# FOC_Drive.net
KiCad netlist of a schematic drawn in Altium Designer
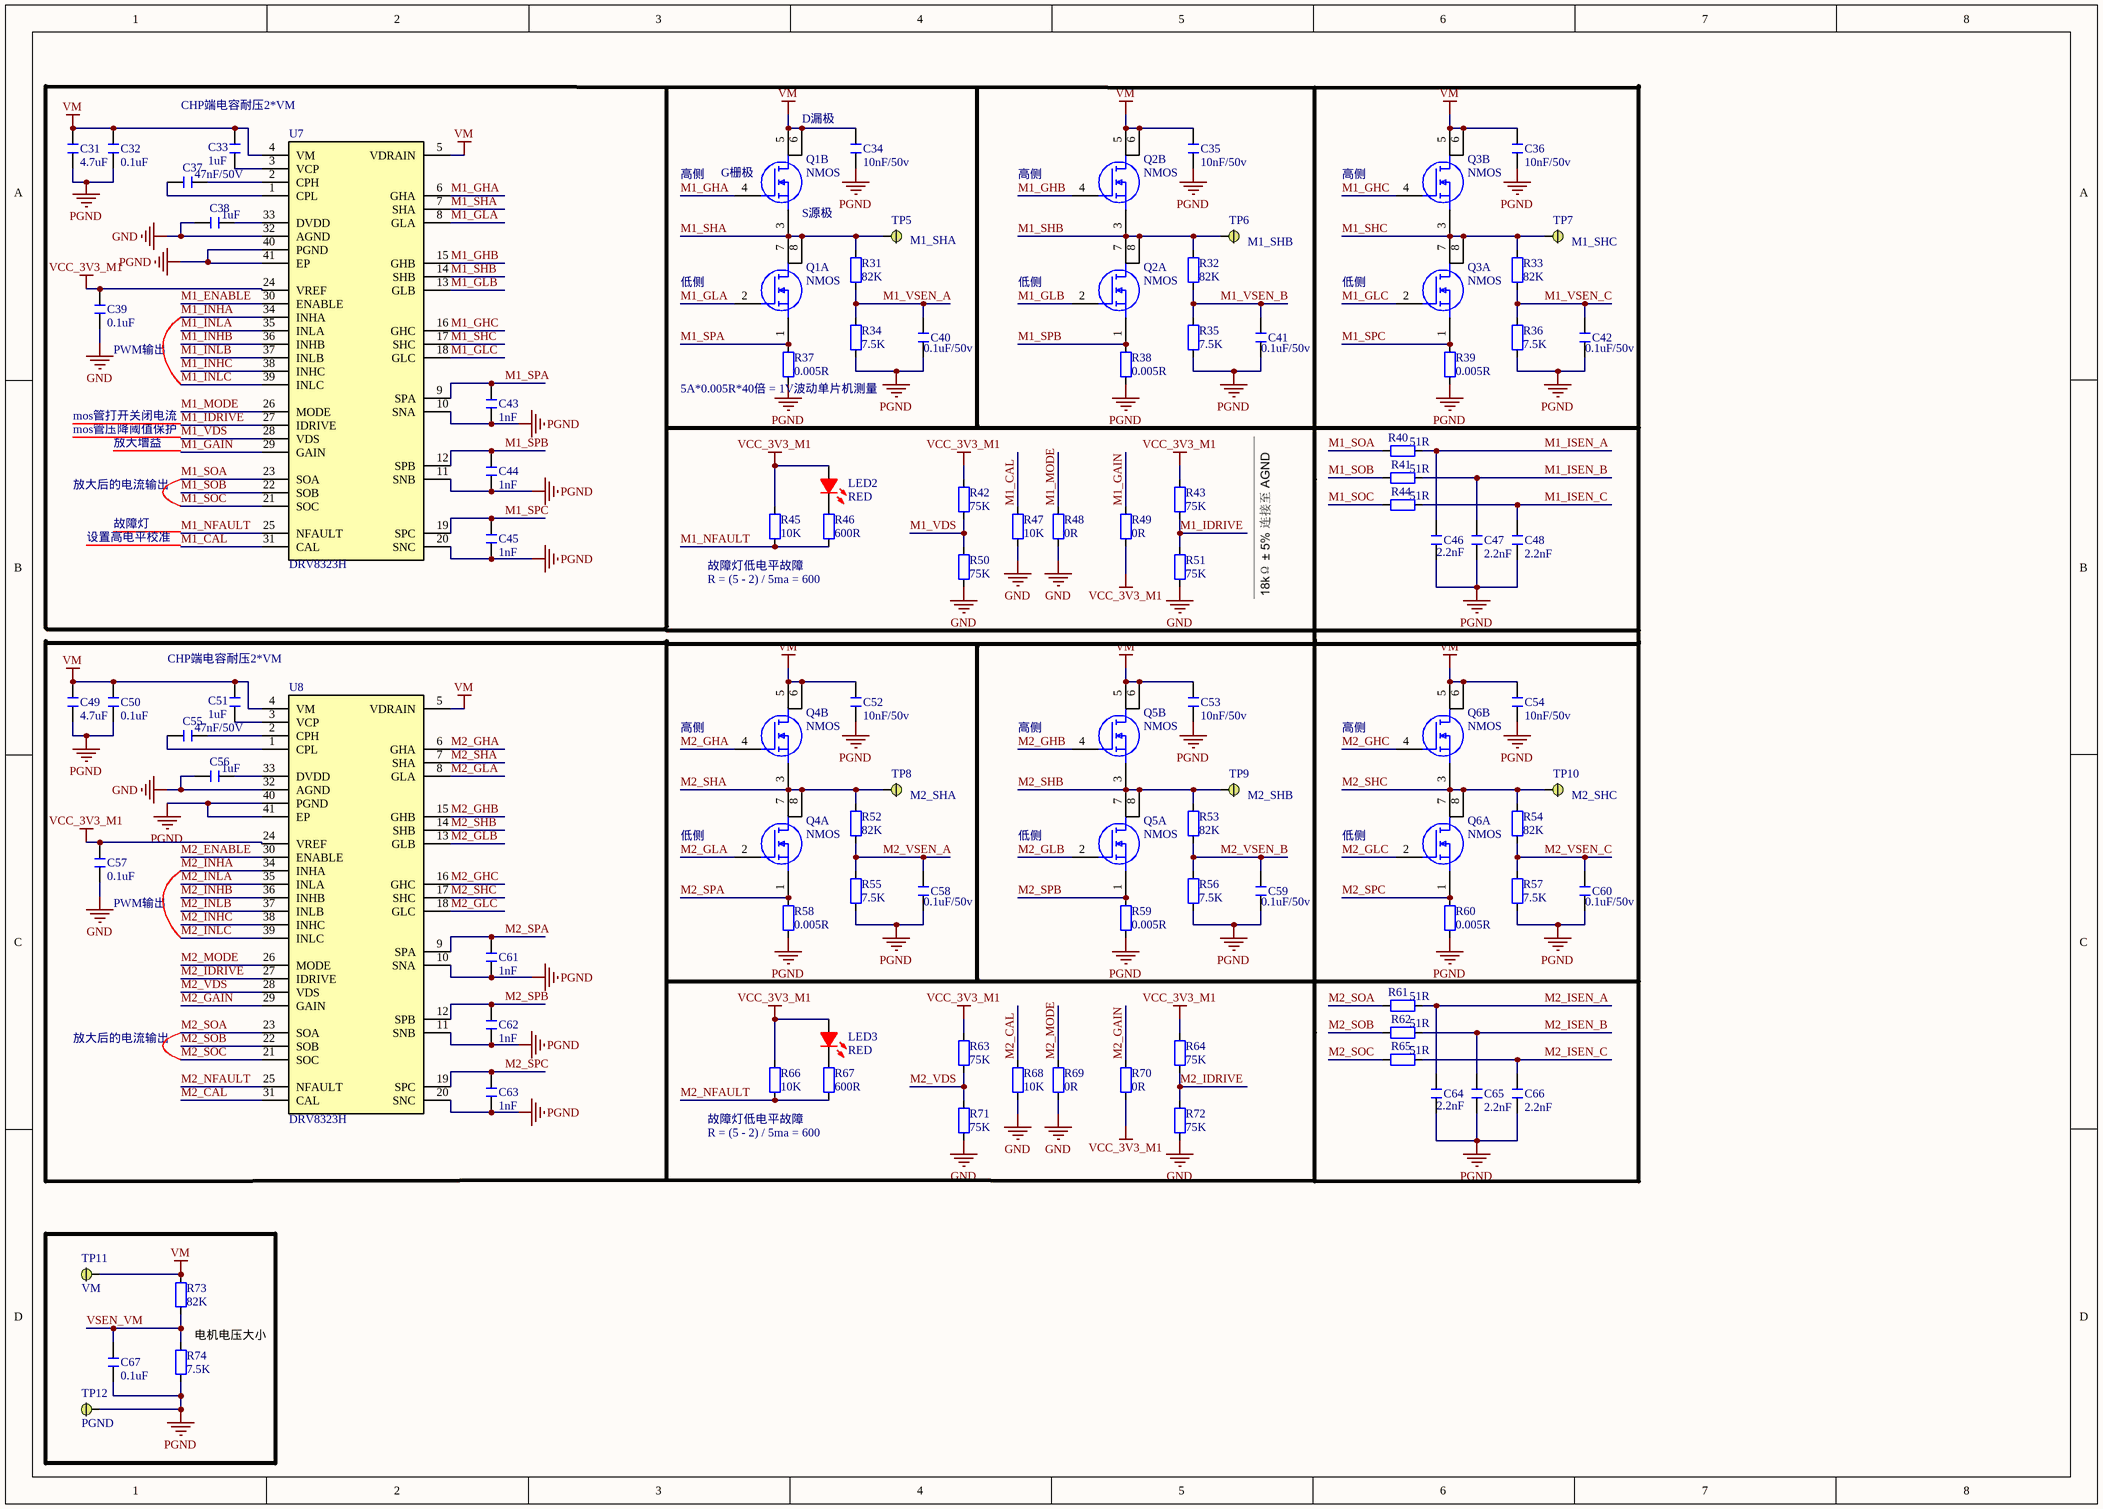
[diagram p0: FOC_Drive.SchDoc]

(export (version "E")
  (design (tool "Eeschema 10.0.6"))
  (components
    (comp (ref "C31")
      (value "4.7uF")
      (footprint "C 0603_L")
      (description "贴片电容")
      (libsource (lib "0.1 电阻_电容_电感") (part "C"))
    )
    (comp (ref "C32")
      (value "0.1uF")
      (footprint "C 0603_L")
      (description "贴片电容")
      (libsource (lib "0.1 电阻_电容_电感") (part "C"))
    )
    (comp (ref "C33")
      (value "1uF")
      (footprint "C 0603_L")
      (description "贴片电容")
      (libsource (lib "0.1 电阻_电容_电感") (part "C"))
    )
    (comp (ref "C34")
      (value "10nF/50v")
      (footprint "C 0603_L")
      (description "贴片电容")
      (libsource (lib "0.1 电阻_电容_电感") (part "C"))
    )
    (comp (ref "C35")
      (value "10nF/50v")
      (footprint "C 0603_L")
      (description "贴片电容")
      (libsource (lib "0.1 电阻_电容_电感") (part "C"))
    )
    (comp (ref "C36")
      (value "10nF/50v")
      (footprint "C 0603_L")
      (description "贴片电容")
      (libsource (lib "0.1 电阻_电容_电感") (part "C"))
    )
    (comp (ref "C37")
      (value "47nF/50V")
      (footprint "C 0603_L")
      (description "贴片电容")
      (libsource (lib "0.1 电阻_电容_电感") (part "C"))
    )
    (comp (ref "C38")
      (value "1uF")
      (footprint "C 0603_L")
      (description "贴片电容")
      (libsource (lib "0.1 电阻_电容_电感") (part "C"))
    )
    (comp (ref "C39")
      (value "0.1uF")
      (footprint "C 0603_L")
      (description "贴片电容")
      (libsource (lib "0.1 电阻_电容_电感") (part "C"))
    )
    (comp (ref "C40")
      (value "0.1uF/50v")
      (footprint "C 0603_L")
      (description "贴片电容")
      (libsource (lib "0.1 电阻_电容_电感") (part "C"))
    )
    (comp (ref "C41")
      (value "0.1uF/50v")
      (footprint "C 0603_L")
      (description "贴片电容")
      (libsource (lib "0.1 电阻_电容_电感") (part "C"))
    )
    (comp (ref "C42")
      (value "0.1uF/50v")
      (footprint "C 0603_L")
      (description "贴片电容")
      (libsource (lib "0.1 电阻_电容_电感") (part "C"))
    )
    (comp (ref "C43")
      (value "1nF")
      (footprint "C 0603_L")
      (description "贴片电容")
      (libsource (lib "0.1 电阻_电容_电感") (part "C"))
    )
    (comp (ref "C44")
      (value "1nF")
      (footprint "C 0603_L")
      (description "贴片电容")
      (libsource (lib "0.1 电阻_电容_电感") (part "C"))
    )
    (comp (ref "C45")
      (value "1nF")
      (footprint "C 0603_L")
      (description "贴片电容")
      (libsource (lib "0.1 电阻_电容_电感") (part "C"))
    )
    (comp (ref "C46")
      (value "2.2nF")
      (footprint "C 0603_L")
      (description "贴片电容")
      (libsource (lib "0.1 电阻_电容_电感") (part "C"))
    )
    (comp (ref "C47")
      (value "2.2nF")
      (footprint "C 0603_L")
      (description "贴片电容")
      (libsource (lib "0.1 电阻_电容_电感") (part "C"))
    )
    (comp (ref "C48")
      (value "2.2nF")
      (footprint "C 0603_L")
      (description "贴片电容")
      (libsource (lib "0.1 电阻_电容_电感") (part "C"))
    )
    (comp (ref "C49")
      (value "4.7uF")
      (footprint "C 0603_L")
      (description "贴片电容")
      (libsource (lib "0.1 电阻_电容_电感") (part "C"))
    )
    (comp (ref "C50")
      (value "0.1uF")
      (footprint "C 0603_L")
      (description "贴片电容")
      (libsource (lib "0.1 电阻_电容_电感") (part "C"))
    )
    (comp (ref "C51")
      (value "1uF")
      (footprint "C 0603_L")
      (description "贴片电容")
      (libsource (lib "0.1 电阻_电容_电感") (part "C"))
    )
    (comp (ref "C52")
      (value "10nF/50v")
      (footprint "C 0603_L")
      (description "贴片电容")
      (libsource (lib "0.1 电阻_电容_电感") (part "C"))
    )
    (comp (ref "C53")
      (value "10nF/50v")
      (footprint "C 0603_L")
      (description "贴片电容")
      (libsource (lib "0.1 电阻_电容_电感") (part "C"))
    )
    (comp (ref "C54")
      (value "10nF/50v")
      (footprint "C 0603_L")
      (description "贴片电容")
      (libsource (lib "0.1 电阻_电容_电感") (part "C"))
    )
    (comp (ref "C55")
      (value "47nF/50V")
      (footprint "C 0603_L")
      (description "贴片电容")
      (libsource (lib "0.1 电阻_电容_电感") (part "C"))
    )
    (comp (ref "C56")
      (value "1uF")
      (footprint "C 0603_L")
      (description "贴片电容")
      (libsource (lib "0.1 电阻_电容_电感") (part "C"))
    )
    (comp (ref "C57")
      (value "0.1uF")
      (footprint "C 0603_L")
      (description "贴片电容")
      (libsource (lib "0.1 电阻_电容_电感") (part "C"))
    )
    (comp (ref "C58")
      (value "0.1uF/50v")
      (footprint "C 0603_L")
      (description "贴片电容")
      (libsource (lib "0.1 电阻_电容_电感") (part "C"))
    )
    (comp (ref "C59")
      (value "0.1uF/50v")
      (footprint "C 0603_L")
      (description "贴片电容")
      (libsource (lib "0.1 电阻_电容_电感") (part "C"))
    )
    (comp (ref "C60")
      (value "0.1uF/50v")
      (footprint "C 0603_L")
      (description "贴片电容")
      (libsource (lib "0.1 电阻_电容_电感") (part "C"))
    )
    (comp (ref "C61")
      (value "1nF")
      (footprint "C 0603_L")
      (description "贴片电容")
      (libsource (lib "0.1 电阻_电容_电感") (part "C"))
    )
    (comp (ref "C62")
      (value "1nF")
      (footprint "C 0603_L")
      (description "贴片电容")
      (libsource (lib "0.1 电阻_电容_电感") (part "C"))
    )
    (comp (ref "C63")
      (value "1nF")
      (footprint "C 0603_L")
      (description "贴片电容")
      (libsource (lib "0.1 电阻_电容_电感") (part "C"))
    )
    (comp (ref "C64")
      (value "2.2nF")
      (footprint "C 0603_L")
      (description "贴片电容")
      (libsource (lib "0.1 电阻_电容_电感") (part "C"))
    )
    (comp (ref "C65")
      (value "2.2nF")
      (footprint "C 0603_L")
      (description "贴片电容")
      (libsource (lib "0.1 电阻_电容_电感") (part "C"))
    )
    (comp (ref "C66")
      (value "2.2nF")
      (footprint "C 0603_L")
      (description "贴片电容")
      (libsource (lib "0.1 电阻_电容_电感") (part "C"))
    )
    (comp (ref "C67")
      (value "0.1uF")
      (footprint "C 0603_L")
      (description "贴片电容")
      (libsource (lib "0.1 电阻_电容_电感") (part "C"))
    )
    (comp (ref "LED2")
      (value "RED")
      (footprint "LED_0603R")
      (description "贴片LED 0603 红色")
      (libsource (lib "0.6 发光二极管") (part "LED_R"))
    )
    (comp (ref "LED3")
      (value "RED")
      (footprint "LED_0603R")
      (description "贴片LED 0603 红色")
      (libsource (lib "0.6 发光二极管") (part "LED_R"))
    )
    (comp (ref "Q1")
      (value "NMOS")
      (footprint "DFN-8_L5.8-W4.9-P1.27-LS6.0-BL")
      (description "NMOS，100V，35A，2 channel")
      (libsource (lib "0.4 场效应管") (part "NCEP01ND35AG"))
    )
    (comp (ref "Q2")
      (value "NMOS")
      (footprint "DFN-8_L5.8-W4.9-P1.27-LS6.0-BL")
      (description "NMOS，100V，35A，2 channel")
      (libsource (lib "0.4 场效应管") (part "NCEP01ND35AG"))
    )
    (comp (ref "Q3")
      (value "NMOS")
      (footprint "DFN-8_L5.8-W4.9-P1.27-LS6.0-BL")
      (description "NMOS，100V，35A，2 channel")
      (libsource (lib "0.4 场效应管") (part "NCEP01ND35AG"))
    )
    (comp (ref "Q4")
      (value "NMOS")
      (footprint "DFN-8_L5.8-W4.9-P1.27-LS6.0-BL")
      (description "NMOS，100V，35A，2 channel")
      (libsource (lib "0.4 场效应管") (part "NCEP01ND35AG"))
    )
    (comp (ref "Q5")
      (value "NMOS")
      (footprint "DFN-8_L5.8-W4.9-P1.27-LS6.0-BL")
      (description "NMOS，100V，35A，2 channel")
      (libsource (lib "0.4 场效应管") (part "NCEP01ND35AG"))
    )
    (comp (ref "Q6")
      (value "NMOS")
      (footprint "DFN-8_L5.8-W4.9-P1.27-LS6.0-BL")
      (description "NMOS，100V，35A，2 channel")
      (libsource (lib "0.4 场效应管") (part "NCEP01ND35AG"))
    )
    (comp (ref "R31")
      (value "82K")
      (footprint "R 0603_L")
      (description "贴片电阻")
      (libsource (lib "0.1 电阻_电容_电感") (part "R"))
    )
    (comp (ref "R32")
      (value "82K")
      (footprint "R 0603_L")
      (description "贴片电阻")
      (libsource (lib "0.1 电阻_电容_电感") (part "R"))
    )
    (comp (ref "R33")
      (value "82K")
      (footprint "R 0603_L")
      (description "贴片电阻")
      (libsource (lib "0.1 电阻_电容_电感") (part "R"))
    )
    (comp (ref "R34")
      (value "7.5K")
      (footprint "R 0603_L")
      (description "贴片电阻")
      (libsource (lib "0.1 电阻_电容_电感") (part "R"))
    )
    (comp (ref "R35")
      (value "7.5K")
      (footprint "R 0603_L")
      (description "贴片电阻")
      (libsource (lib "0.1 电阻_电容_电感") (part "R"))
    )
    (comp (ref "R36")
      (value "7.5K")
      (footprint "R 0603_L")
      (description "贴片电阻")
      (libsource (lib "0.1 电阻_电容_电感") (part "R"))
    )
    (comp (ref "R37")
      (value "0.005R")
      (footprint "R 2512_L")
      (description "贴片电阻")
      (libsource (lib "0.1 电阻_电容_电感") (part "R"))
    )
    (comp (ref "R38")
      (value "0.005R")
      (footprint "R 2512_L")
      (description "贴片电阻")
      (libsource (lib "0.1 电阻_电容_电感") (part "R"))
    )
    (comp (ref "R39")
      (value "0.005R")
      (footprint "R 2512_L")
      (description "贴片电阻")
      (libsource (lib "0.1 电阻_电容_电感") (part "R"))
    )
    (comp (ref "R40")
      (value "51R")
      (footprint "R 0603_L")
      (description "贴片电阻")
      (libsource (lib "") (part "R_2"))
    )
    (comp (ref "R41")
      (value "51R")
      (footprint "R 0603_L")
      (description "贴片电阻")
      (libsource (lib "") (part "R_2"))
    )
    (comp (ref "R42")
      (value "75K")
      (footprint "R 0603_L")
      (description "贴片电阻")
      (libsource (lib "") (part "R_1"))
    )
    (comp (ref "R43")
      (value "75K")
      (footprint "R 0603_L")
      (description "贴片电阻")
      (libsource (lib "") (part "R_1"))
    )
    (comp (ref "R44")
      (value "51R")
      (footprint "R 0603_L")
      (description "贴片电阻")
      (libsource (lib "") (part "R_2"))
    )
    (comp (ref "R45")
      (value "10K")
      (footprint "R 0603_L")
      (description "贴片电阻")
      (libsource (lib "") (part "R_1"))
    )
    (comp (ref "R46")
      (value "600R")
      (footprint "R 0603_L")
      (description "贴片电阻")
      (libsource (lib "") (part "R_1"))
    )
    (comp (ref "R47")
      (value "10K")
      (footprint "R 0603_L")
      (description "贴片电阻")
      (libsource (lib "") (part "R_1"))
    )
    (comp (ref "R48")
      (value "0R")
      (footprint "R 0603_L")
      (description "贴片电阻")
      (libsource (lib "0.1 电阻_电容_电感") (part "R"))
    )
    (comp (ref "R49")
      (value "0R")
      (footprint "R 0603_L")
      (description "贴片电阻")
      (libsource (lib "0.1 电阻_电容_电感") (part "R"))
    )
    (comp (ref "R50")
      (value "75K")
      (footprint "R 0603_L")
      (description "贴片电阻")
      (libsource (lib "") (part "R_1"))
    )
    (comp (ref "R51")
      (value "75K")
      (footprint "R 0603_L")
      (description "贴片电阻")
      (libsource (lib "") (part "R_1"))
    )
    (comp (ref "R52")
      (value "82K")
      (footprint "R 0603_L")
      (description "贴片电阻")
      (libsource (lib "0.1 电阻_电容_电感") (part "R"))
    )
    (comp (ref "R53")
      (value "82K")
      (footprint "R 0603_L")
      (description "贴片电阻")
      (libsource (lib "0.1 电阻_电容_电感") (part "R"))
    )
    (comp (ref "R54")
      (value "82K")
      (footprint "R 0603_L")
      (description "贴片电阻")
      (libsource (lib "0.1 电阻_电容_电感") (part "R"))
    )
    (comp (ref "R55")
      (value "7.5K")
      (footprint "R 0603_L")
      (description "贴片电阻")
      (libsource (lib "0.1 电阻_电容_电感") (part "R"))
    )
    (comp (ref "R56")
      (value "7.5K")
      (footprint "R 0603_L")
      (description "贴片电阻")
      (libsource (lib "0.1 电阻_电容_电感") (part "R"))
    )
    (comp (ref "R57")
      (value "7.5K")
      (footprint "R 0603_L")
      (description "贴片电阻")
      (libsource (lib "0.1 电阻_电容_电感") (part "R"))
    )
    (comp (ref "R58")
      (value "0.005R")
      (footprint "R 2512_L")
      (description "贴片电阻")
      (libsource (lib "0.1 电阻_电容_电感") (part "R"))
    )
    (comp (ref "R59")
      (value "0.005R")
      (footprint "R 2512_L")
      (description "贴片电阻")
      (libsource (lib "0.1 电阻_电容_电感") (part "R"))
    )
    (comp (ref "R60")
      (value "0.005R")
      (footprint "R 2512_L")
      (description "贴片电阻")
      (libsource (lib "0.1 电阻_电容_电感") (part "R"))
    )
    (comp (ref "R61")
      (value "51R")
      (footprint "R 0603_L")
      (description "贴片电阻")
      (libsource (lib "") (part "R_2"))
    )
    (comp (ref "R62")
      (value "51R")
      (footprint "R 0603_L")
      (description "贴片电阻")
      (libsource (lib "") (part "R_2"))
    )
    (comp (ref "R63")
      (value "75K")
      (footprint "R 0603_L")
      (description "贴片电阻")
      (libsource (lib "") (part "R_1"))
    )
    (comp (ref "R64")
      (value "75K")
      (footprint "R 0603_L")
      (description "贴片电阻")
      (libsource (lib "") (part "R_1"))
    )
    (comp (ref "R65")
      (value "51R")
      (footprint "R 0603_L")
      (description "贴片电阻")
      (libsource (lib "") (part "R_2"))
    )
    (comp (ref "R66")
      (value "10K")
      (footprint "R 0603_L")
      (description "贴片电阻")
      (libsource (lib "") (part "R_1"))
    )
    (comp (ref "R67")
      (value "600R")
      (footprint "R 0603_L")
      (description "贴片电阻")
      (libsource (lib "") (part "R_1"))
    )
    (comp (ref "R68")
      (value "10K")
      (footprint "R 0603_L")
      (description "贴片电阻")
      (libsource (lib "") (part "R_1"))
    )
    (comp (ref "R69")
      (value "0R")
      (footprint "R 0603_L")
      (description "贴片电阻")
      (libsource (lib "0.1 电阻_电容_电感") (part "R"))
    )
    (comp (ref "R70")
      (value "0R")
      (footprint "R 0603_L")
      (description "贴片电阻")
      (libsource (lib "0.1 电阻_电容_电感") (part "R"))
    )
    (comp (ref "R71")
      (value "75K")
      (footprint "R 0603_L")
      (description "贴片电阻")
      (libsource (lib "") (part "R_1"))
    )
    (comp (ref "R72")
      (value "75K")
      (footprint "R 0603_L")
      (description "贴片电阻")
      (libsource (lib "") (part "R_1"))
    )
    (comp (ref "R73")
      (value "82K")
      (footprint "R 0603_L")
      (description "贴片电阻")
      (libsource (lib "") (part "R_1"))
    )
    (comp (ref "R74")
      (value "7.5K")
      (footprint "R 0603_L")
      (description "贴片电阻")
      (libsource (lib "") (part "R_1"))
    )
    (comp (ref "TP5") (value "M1_SHA") (footprint "TP_RECT_2x2") (libsource (lib "0.5 测试点-焊盘") (part "TP")))
    (comp (ref "TP6") (value "M1_SHB") (footprint "TP_RECT_2x2") (libsource (lib "0.5 测试点-焊盘") (part "TP")))
    (comp (ref "TP7") (value "M1_SHC") (footprint "TP_RECT_2x2") (libsource (lib "0.5 测试点-焊盘") (part "TP")))
    (comp (ref "TP8") (value "M2_SHA") (footprint "TP_RECT_2x2") (libsource (lib "0.5 测试点-焊盘") (part "TP")))
    (comp (ref "TP9") (value "M2_SHB") (footprint "TP_RECT_2x2") (libsource (lib "0.5 测试点-焊盘") (part "TP")))
    (comp (ref "TP10") (value "M2_SHC") (footprint "TP_RECT_2x2") (libsource (lib "0.5 测试点-焊盘") (part "TP")))
    (comp (ref "TP11") (value "VM") (footprint "TP_RECT_2x2") (libsource (lib "0.5 测试点-焊盘") (part "TP")))
    (comp (ref "TP12") (value "PGND") (footprint "TP_RECT_2x2") (libsource (lib "0.5 测试点-焊盘") (part "TP")))
    (comp (ref "U7")
      (value "DRV8323H")
      (footprint "QFN50P600X600X80-41N-D")
      (description "三相智能栅极驱动器")
      (fields (field (name "MANUFACTURER_PART_NUMBER") "DRV8323"))
      (libsource (lib "0.4 场效应管") (part "DRV8323H"))
    )
    (comp (ref "U8")
      (value "DRV8323H")
      (footprint "QFN50P600X600X80-41N-D")
      (description "三相智能栅极驱动器")
      (fields (field (name "MANUFACTURER_PART_NUMBER") "DRV8323"))
      (libsource (lib "0.4 场效应管") (part "DRV8323H"))
    )
  )
  (nets
    (net (code "1") (name "/M1_CAL") (class "Default")
      (node (ref "R47") (pin "1") (pinfunction "1_1") (pintype "passive"))
      (node (ref "U7") (pin "31") (pinfunction "CAL_31") (pintype "passive"))
    )
    (net (code "2") (name "/M1_ENABLE") (class "Default")
      (node (ref "U7") (pin "30") (pinfunction "ENABLE_30") (pintype "passive"))
    )
    (net (code "3") (name "/M1_GAIN") (class "Default")
      (node (ref "R49") (pin "2") (pinfunction "2_2") (pintype "passive"))
      (node (ref "U7") (pin "29") (pinfunction "GAIN_29") (pintype "passive"))
    )
    (net (code "4") (name "/M1_GHA") (class "Default")
      (node (ref "Q1") (pin "4") (pinfunction "G2_4") (pintype "passive"))
      (node (ref "U7") (pin "6") (pinfunction "GHA_6") (pintype "passive"))
    )
    (net (code "5") (name "/M1_GHB") (class "Default")
      (node (ref "Q2") (pin "4") (pinfunction "G2_4") (pintype "passive"))
      (node (ref "U7") (pin "15") (pinfunction "GHB_15") (pintype "passive"))
    )
    (net (code "6") (name "/M1_GHC") (class "Default")
      (node (ref "Q3") (pin "4") (pinfunction "G2_4") (pintype "passive"))
      (node (ref "U7") (pin "16") (pinfunction "GHC_16") (pintype "passive"))
    )
    (net (code "7") (name "/M1_GLA") (class "Default")
      (node (ref "Q1") (pin "2") (pinfunction "G1_2") (pintype "passive"))
      (node (ref "U7") (pin "8") (pinfunction "GLA_8") (pintype "passive"))
    )
    (net (code "8") (name "/M1_GLB") (class "Default")
      (node (ref "Q2") (pin "2") (pinfunction "G1_2") (pintype "passive"))
      (node (ref "U7") (pin "13") (pinfunction "GLB_13") (pintype "passive"))
    )
    (net (code "9") (name "/M1_GLC") (class "Default")
      (node (ref "Q3") (pin "2") (pinfunction "G1_2") (pintype "passive"))
      (node (ref "U7") (pin "18") (pinfunction "GLC_18") (pintype "passive"))
    )
    (net (code "10") (name "/M1_IDRIVE") (class "Default")
      (node (ref "R43") (pin "2") (pinfunction "2_2") (pintype "passive"))
      (node (ref "R51") (pin "1") (pinfunction "1_1") (pintype "passive"))
      (node (ref "U7") (pin "27") (pinfunction "IDRIVE_27") (pintype "passive"))
    )
    (net (code "11") (name "/M1_INHA") (class "Default")
      (node (ref "U7") (pin "34") (pinfunction "INHA_34") (pintype "passive"))
    )
    (net (code "12") (name "/M1_INHB") (class "Default")
      (node (ref "U7") (pin "36") (pinfunction "INHB_36") (pintype "passive"))
    )
    (net (code "13") (name "/M1_INHC") (class "Default")
      (node (ref "U7") (pin "38") (pinfunction "INHC_38") (pintype "passive"))
    )
    (net (code "14") (name "/M1_INLA") (class "Default")
      (node (ref "U7") (pin "35") (pinfunction "INLA_35") (pintype "passive"))
    )
    (net (code "15") (name "/M1_INLB") (class "Default")
      (node (ref "U7") (pin "37") (pinfunction "INLB_37") (pintype "passive"))
    )
    (net (code "16") (name "/M1_INLC") (class "Default")
      (node (ref "U7") (pin "39") (pinfunction "INLC_39") (pintype "passive"))
    )
    (net (code "17") (name "/M1_ISEN_A") (class "Default")
      (node (ref "C46") (pin "2") (pinfunction "2_2") (pintype "passive"))
      (node (ref "R40") (pin "1") (pinfunction "1_1") (pintype "passive"))
    )
    (net (code "18") (name "/M1_ISEN_B") (class "Default")
      (node (ref "C47") (pin "2") (pinfunction "2_2") (pintype "passive"))
      (node (ref "R41") (pin "1") (pinfunction "1_1") (pintype "passive"))
    )
    (net (code "19") (name "/M1_ISEN_C") (class "Default")
      (node (ref "C48") (pin "2") (pinfunction "2_2") (pintype "passive"))
      (node (ref "R44") (pin "1") (pinfunction "1_1") (pintype "passive"))
    )
    (net (code "20") (name "/M1_MODE") (class "Default")
      (node (ref "R48") (pin "2") (pinfunction "2_2") (pintype "passive"))
      (node (ref "U7") (pin "26") (pinfunction "MODE_26") (pintype "passive"))
    )
    (net (code "21") (name "/M1_NFAULT") (class "Default")
      (node (ref "R45") (pin "2") (pinfunction "2_2") (pintype "passive"))
      (node (ref "R46") (pin "2") (pinfunction "2_2") (pintype "passive"))
      (node (ref "U7") (pin "25") (pinfunction "NFAULT_25") (pintype "passive"))
    )
    (net (code "22") (name "/M1_SHA") (class "Default")
      (node (ref "Q1") (pin "3") (pinfunction "S2_3") (pintype "passive"))
      (node (ref "Q1") (pin "7") (pinfunction "D1_7") (pintype "passive"))
      (node (ref "Q1") (pin "8") (pinfunction "D1_8") (pintype "passive"))
      (node (ref "R31") (pin "2") (pinfunction "2_2") (pintype "passive"))
      (node (ref "TP5") (pin "1") (pintype "passive"))
      (node (ref "U7") (pin "7") (pinfunction "SHA_7") (pintype "passive"))
    )
    (net (code "23") (name "/M1_SHB") (class "Default")
      (node (ref "Q2") (pin "3") (pinfunction "S2_3") (pintype "passive"))
      (node (ref "Q2") (pin "7") (pinfunction "D1_7") (pintype "passive"))
      (node (ref "Q2") (pin "8") (pinfunction "D1_8") (pintype "passive"))
      (node (ref "R32") (pin "2") (pinfunction "2_2") (pintype "passive"))
      (node (ref "TP6") (pin "1") (pintype "passive"))
      (node (ref "U7") (pin "14") (pinfunction "SHB_14") (pintype "passive"))
    )
    (net (code "24") (name "/M1_SHC") (class "Default")
      (node (ref "Q3") (pin "3") (pinfunction "S2_3") (pintype "passive"))
      (node (ref "Q3") (pin "7") (pinfunction "D1_7") (pintype "passive"))
      (node (ref "Q3") (pin "8") (pinfunction "D1_8") (pintype "passive"))
      (node (ref "R33") (pin "2") (pinfunction "2_2") (pintype "passive"))
      (node (ref "TP7") (pin "1") (pintype "passive"))
      (node (ref "U7") (pin "17") (pinfunction "SHC_17") (pintype "passive"))
    )
    (net (code "25") (name "/M1_SOA") (class "Default")
      (node (ref "R40") (pin "2") (pinfunction "2_2") (pintype "passive"))
      (node (ref "U7") (pin "23") (pinfunction "SOA_23") (pintype "passive"))
    )
    (net (code "26") (name "/M1_SOB") (class "Default")
      (node (ref "R41") (pin "2") (pinfunction "2_2") (pintype "passive"))
      (node (ref "U7") (pin "22") (pinfunction "SOB_22") (pintype "passive"))
    )
    (net (code "27") (name "/M1_SOC") (class "Default")
      (node (ref "R44") (pin "2") (pinfunction "2_2") (pintype "passive"))
      (node (ref "U7") (pin "21") (pinfunction "SOC_21") (pintype "passive"))
    )
    (net (code "28") (name "/M1_SPA") (class "Default")
      (node (ref "C43") (pin "1") (pinfunction "1_1") (pintype "passive"))
      (node (ref "Q1") (pin "1") (pinfunction "S1_1") (pintype "passive"))
      (node (ref "R37") (pin "2") (pinfunction "2_2") (pintype "passive"))
      (node (ref "U7") (pin "9") (pinfunction "SPA_9") (pintype "passive"))
    )
    (net (code "29") (name "/M1_SPB") (class "Default")
      (node (ref "C44") (pin "1") (pinfunction "1_1") (pintype "passive"))
      (node (ref "Q2") (pin "1") (pinfunction "S1_1") (pintype "passive"))
      (node (ref "R38") (pin "2") (pinfunction "2_2") (pintype "passive"))
      (node (ref "U7") (pin "12") (pinfunction "SPB_12") (pintype "passive"))
    )
    (net (code "30") (name "/M1_SPC") (class "Default")
      (node (ref "C45") (pin "1") (pinfunction "1_1") (pintype "passive"))
      (node (ref "Q3") (pin "1") (pinfunction "S1_1") (pintype "passive"))
      (node (ref "R39") (pin "2") (pinfunction "2_2") (pintype "passive"))
      (node (ref "U7") (pin "19") (pinfunction "SPC_19") (pintype "passive"))
    )
    (net (code "31") (name "/M1_VDS") (class "Default")
      (node (ref "R42") (pin "2") (pinfunction "2_2") (pintype "passive"))
      (node (ref "R50") (pin "1") (pinfunction "1_1") (pintype "passive"))
      (node (ref "U7") (pin "28") (pinfunction "VDS_28") (pintype "passive"))
    )
    (net (code "32") (name "/M1_VSEN_A") (class "Default")
      (node (ref "C40") (pin "2") (pinfunction "2_2") (pintype "passive"))
      (node (ref "R31") (pin "1") (pinfunction "1_1") (pintype "passive"))
      (node (ref "R34") (pin "2") (pinfunction "2_2") (pintype "passive"))
    )
    (net (code "33") (name "/M1_VSEN_B") (class "Default")
      (node (ref "C41") (pin "2") (pinfunction "2_2") (pintype "passive"))
      (node (ref "R32") (pin "1") (pinfunction "1_1") (pintype "passive"))
      (node (ref "R35") (pin "2") (pinfunction "2_2") (pintype "passive"))
    )
    (net (code "34") (name "/M1_VSEN_C") (class "Default")
      (node (ref "C42") (pin "2") (pinfunction "2_2") (pintype "passive"))
      (node (ref "R33") (pin "1") (pinfunction "1_1") (pintype "passive"))
      (node (ref "R36") (pin "2") (pinfunction "2_2") (pintype "passive"))
    )
    (net (code "35") (name "/M2_CAL") (class "Default")
      (node (ref "R68") (pin "1") (pinfunction "1_1") (pintype "passive"))
      (node (ref "U8") (pin "31") (pinfunction "CAL_31") (pintype "passive"))
    )
    (net (code "36") (name "/M2_ENABLE") (class "Default")
      (node (ref "U8") (pin "30") (pinfunction "ENABLE_30") (pintype "passive"))
    )
    (net (code "37") (name "/M2_GAIN") (class "Default")
      (node (ref "R70") (pin "2") (pinfunction "2_2") (pintype "passive"))
      (node (ref "U8") (pin "29") (pinfunction "GAIN_29") (pintype "passive"))
    )
    (net (code "38") (name "/M2_GHA") (class "Default")
      (node (ref "Q4") (pin "4") (pinfunction "G2_4") (pintype "passive"))
      (node (ref "U8") (pin "6") (pinfunction "GHA_6") (pintype "passive"))
    )
    (net (code "39") (name "/M2_GHB") (class "Default")
      (node (ref "Q5") (pin "4") (pinfunction "G2_4") (pintype "passive"))
      (node (ref "U8") (pin "15") (pinfunction "GHB_15") (pintype "passive"))
    )
    (net (code "40") (name "/M2_GHC") (class "Default")
      (node (ref "Q6") (pin "4") (pinfunction "G2_4") (pintype "passive"))
      (node (ref "U8") (pin "16") (pinfunction "GHC_16") (pintype "passive"))
    )
    (net (code "41") (name "/M2_GLA") (class "Default")
      (node (ref "Q4") (pin "2") (pinfunction "G1_2") (pintype "passive"))
      (node (ref "U8") (pin "8") (pinfunction "GLA_8") (pintype "passive"))
    )
    (net (code "42") (name "/M2_GLB") (class "Default")
      (node (ref "Q5") (pin "2") (pinfunction "G1_2") (pintype "passive"))
      (node (ref "U8") (pin "13") (pinfunction "GLB_13") (pintype "passive"))
    )
    (net (code "43") (name "/M2_GLC") (class "Default")
      (node (ref "Q6") (pin "2") (pinfunction "G1_2") (pintype "passive"))
      (node (ref "U8") (pin "18") (pinfunction "GLC_18") (pintype "passive"))
    )
    (net (code "44") (name "/M2_IDRIVE") (class "Default")
      (node (ref "R64") (pin "2") (pinfunction "2_2") (pintype "passive"))
      (node (ref "R72") (pin "1") (pinfunction "1_1") (pintype "passive"))
      (node (ref "U8") (pin "27") (pinfunction "IDRIVE_27") (pintype "passive"))
    )
    (net (code "45") (name "/M2_INHA") (class "Default")
      (node (ref "U8") (pin "34") (pinfunction "INHA_34") (pintype "passive"))
    )
    (net (code "46") (name "/M2_INHB") (class "Default")
      (node (ref "U8") (pin "36") (pinfunction "INHB_36") (pintype "passive"))
    )
    (net (code "47") (name "/M2_INHC") (class "Default")
      (node (ref "U8") (pin "38") (pinfunction "INHC_38") (pintype "passive"))
    )
    (net (code "48") (name "/M2_INLA") (class "Default")
      (node (ref "U8") (pin "35") (pinfunction "INLA_35") (pintype "passive"))
    )
    (net (code "49") (name "/M2_INLB") (class "Default")
      (node (ref "U8") (pin "37") (pinfunction "INLB_37") (pintype "passive"))
    )
    (net (code "50") (name "/M2_INLC") (class "Default")
      (node (ref "U8") (pin "39") (pinfunction "INLC_39") (pintype "passive"))
    )
    (net (code "51") (name "/M2_ISEN_A") (class "Default")
      (node (ref "C64") (pin "2") (pinfunction "2_2") (pintype "passive"))
      (node (ref "R61") (pin "1") (pinfunction "1_1") (pintype "passive"))
    )
    (net (code "52") (name "/M2_ISEN_B") (class "Default")
      (node (ref "C65") (pin "2") (pinfunction "2_2") (pintype "passive"))
      (node (ref "R62") (pin "1") (pinfunction "1_1") (pintype "passive"))
    )
    (net (code "53") (name "/M2_ISEN_C") (class "Default")
      (node (ref "C66") (pin "2") (pinfunction "2_2") (pintype "passive"))
      (node (ref "R65") (pin "1") (pinfunction "1_1") (pintype "passive"))
    )
    (net (code "54") (name "/M2_MODE") (class "Default")
      (node (ref "R69") (pin "2") (pinfunction "2_2") (pintype "passive"))
      (node (ref "U8") (pin "26") (pinfunction "MODE_26") (pintype "passive"))
    )
    (net (code "55") (name "/M2_NFAULT") (class "Default")
      (node (ref "R66") (pin "2") (pinfunction "2_2") (pintype "passive"))
      (node (ref "R67") (pin "2") (pinfunction "2_2") (pintype "passive"))
      (node (ref "U8") (pin "25") (pinfunction "NFAULT_25") (pintype "passive"))
    )
    (net (code "56") (name "/M2_SHA") (class "Default")
      (node (ref "Q4") (pin "3") (pinfunction "S2_3") (pintype "passive"))
      (node (ref "Q4") (pin "7") (pinfunction "D1_7") (pintype "passive"))
      (node (ref "Q4") (pin "8") (pinfunction "D1_8") (pintype "passive"))
      (node (ref "R52") (pin "2") (pinfunction "2_2") (pintype "passive"))
      (node (ref "TP8") (pin "1") (pintype "passive"))
      (node (ref "U8") (pin "7") (pinfunction "SHA_7") (pintype "passive"))
    )
    (net (code "57") (name "/M2_SHB") (class "Default")
      (node (ref "Q5") (pin "3") (pinfunction "S2_3") (pintype "passive"))
      (node (ref "Q5") (pin "7") (pinfunction "D1_7") (pintype "passive"))
      (node (ref "Q5") (pin "8") (pinfunction "D1_8") (pintype "passive"))
      (node (ref "R53") (pin "2") (pinfunction "2_2") (pintype "passive"))
      (node (ref "TP9") (pin "1") (pintype "passive"))
      (node (ref "U8") (pin "14") (pinfunction "SHB_14") (pintype "passive"))
    )
    (net (code "58") (name "/M2_SHC") (class "Default")
      (node (ref "Q6") (pin "3") (pinfunction "S2_3") (pintype "passive"))
      (node (ref "Q6") (pin "7") (pinfunction "D1_7") (pintype "passive"))
      (node (ref "Q6") (pin "8") (pinfunction "D1_8") (pintype "passive"))
      (node (ref "R54") (pin "2") (pinfunction "2_2") (pintype "passive"))
      (node (ref "TP10") (pin "1") (pintype "passive"))
      (node (ref "U8") (pin "17") (pinfunction "SHC_17") (pintype "passive"))
    )
    (net (code "59") (name "/M2_SOA") (class "Default")
      (node (ref "R61") (pin "2") (pinfunction "2_2") (pintype "passive"))
      (node (ref "U8") (pin "23") (pinfunction "SOA_23") (pintype "passive"))
    )
    (net (code "60") (name "/M2_SOB") (class "Default")
      (node (ref "R62") (pin "2") (pinfunction "2_2") (pintype "passive"))
      (node (ref "U8") (pin "22") (pinfunction "SOB_22") (pintype "passive"))
    )
    (net (code "61") (name "/M2_SOC") (class "Default")
      (node (ref "R65") (pin "2") (pinfunction "2_2") (pintype "passive"))
      (node (ref "U8") (pin "21") (pinfunction "SOC_21") (pintype "passive"))
    )
    (net (code "62") (name "/M2_SPA") (class "Default")
      (node (ref "C61") (pin "1") (pinfunction "1_1") (pintype "passive"))
      (node (ref "Q4") (pin "1") (pinfunction "S1_1") (pintype "passive"))
      (node (ref "R58") (pin "2") (pinfunction "2_2") (pintype "passive"))
      (node (ref "U8") (pin "9") (pinfunction "SPA_9") (pintype "passive"))
    )
    (net (code "63") (name "/M2_SPB") (class "Default")
      (node (ref "C62") (pin "1") (pinfunction "1_1") (pintype "passive"))
      (node (ref "Q5") (pin "1") (pinfunction "S1_1") (pintype "passive"))
      (node (ref "R59") (pin "2") (pinfunction "2_2") (pintype "passive"))
      (node (ref "U8") (pin "12") (pinfunction "SPB_12") (pintype "passive"))
    )
    (net (code "64") (name "/M2_SPC") (class "Default")
      (node (ref "C63") (pin "1") (pinfunction "1_1") (pintype "passive"))
      (node (ref "Q6") (pin "1") (pinfunction "S1_1") (pintype "passive"))
      (node (ref "R60") (pin "2") (pinfunction "2_2") (pintype "passive"))
      (node (ref "U8") (pin "19") (pinfunction "SPC_19") (pintype "passive"))
    )
    (net (code "65") (name "/M2_VDS") (class "Default")
      (node (ref "R63") (pin "2") (pinfunction "2_2") (pintype "passive"))
      (node (ref "R71") (pin "1") (pinfunction "1_1") (pintype "passive"))
      (node (ref "U8") (pin "28") (pinfunction "VDS_28") (pintype "passive"))
    )
    (net (code "66") (name "/M2_VSEN_A") (class "Default")
      (node (ref "C58") (pin "2") (pinfunction "2_2") (pintype "passive"))
      (node (ref "R52") (pin "1") (pinfunction "1_1") (pintype "passive"))
      (node (ref "R55") (pin "2") (pinfunction "2_2") (pintype "passive"))
    )
    (net (code "67") (name "/M2_VSEN_B") (class "Default")
      (node (ref "C59") (pin "2") (pinfunction "2_2") (pintype "passive"))
      (node (ref "R53") (pin "1") (pinfunction "1_1") (pintype "passive"))
      (node (ref "R56") (pin "2") (pinfunction "2_2") (pintype "passive"))
    )
    (net (code "68") (name "/M2_VSEN_C") (class "Default")
      (node (ref "C60") (pin "2") (pinfunction "2_2") (pintype "passive"))
      (node (ref "R54") (pin "1") (pinfunction "1_1") (pintype "passive"))
      (node (ref "R57") (pin "2") (pinfunction "2_2") (pintype "passive"))
    )
    (net (code "69") (name "/VSEN_VM") (class "Default")
      (node (ref "C67") (pin "2") (pinfunction "2_2") (pintype "passive"))
      (node (ref "R73") (pin "2") (pinfunction "2_2") (pintype "passive"))
      (node (ref "R74") (pin "1") (pinfunction "1_1") (pintype "passive"))
    )
    (net (code "70") (name "GND") (class "Default")
      (node (ref "C38") (pin "1") (pinfunction "1_1") (pintype "passive"))
      (node (ref "C39") (pin "1") (pinfunction "1_1") (pintype "passive"))
      (node (ref "C56") (pin "1") (pinfunction "1_1") (pintype "passive"))
      (node (ref "C57") (pin "1") (pinfunction "1_1") (pintype "passive"))
      (node (ref "R47") (pin "2") (pinfunction "2_2") (pintype "passive"))
      (node (ref "R48") (pin "1") (pinfunction "1_1") (pintype "passive"))
      (node (ref "R50") (pin "2") (pinfunction "2_2") (pintype "passive"))
      (node (ref "R51") (pin "2") (pinfunction "2_2") (pintype "passive"))
      (node (ref "R68") (pin "2") (pinfunction "2_2") (pintype "passive"))
      (node (ref "R69") (pin "1") (pinfunction "1_1") (pintype "passive"))
      (node (ref "R71") (pin "2") (pinfunction "2_2") (pintype "passive"))
      (node (ref "R72") (pin "2") (pinfunction "2_2") (pintype "passive"))
      (node (ref "U7") (pin "32") (pinfunction "AGND_32") (pintype "passive"))
      (node (ref "U8") (pin "32") (pinfunction "AGND_32") (pintype "passive"))
    )
    (net (code "71") (name "Net-(LED2--)") (class "Default")
      (node (ref "LED2") (pin "2") (pinfunction "-_2") (pintype "passive"))
      (node (ref "R46") (pin "1") (pinfunction "1_1") (pintype "passive"))
    )
    (net (code "72") (name "Net-(LED3--)") (class "Default")
      (node (ref "LED3") (pin "2") (pinfunction "-_2") (pintype "passive"))
      (node (ref "R67") (pin "1") (pinfunction "1_1") (pintype "passive"))
    )
    (net (code "73") (name "Net-(U7-CPH)") (class "Default")
      (node (ref "C37") (pin "1") (pinfunction "1_1") (pintype "passive"))
      (node (ref "U7") (pin "2") (pinfunction "CPH_2") (pintype "passive"))
    )
    (net (code "74") (name "Net-(U7-CPL)") (class "Default")
      (node (ref "C37") (pin "2") (pinfunction "2_2") (pintype "passive"))
      (node (ref "U7") (pin "1") (pinfunction "CPL_1") (pintype "passive"))
    )
    (net (code "75") (name "Net-(U7-DVDD)") (class "Default")
      (node (ref "C38") (pin "2") (pinfunction "2_2") (pintype "passive"))
      (node (ref "U7") (pin "33") (pinfunction "DVDD_33") (pintype "passive"))
    )
    (net (code "76") (name "Net-(U7-VCP)") (class "Default")
      (node (ref "C33") (pin "1") (pinfunction "1_1") (pintype "passive"))
      (node (ref "U7") (pin "3") (pinfunction "VCP_3") (pintype "passive"))
    )
    (net (code "77") (name "Net-(U8-CPH)") (class "Default")
      (node (ref "C55") (pin "1") (pinfunction "1_1") (pintype "passive"))
      (node (ref "U8") (pin "2") (pinfunction "CPH_2") (pintype "passive"))
    )
    (net (code "78") (name "Net-(U8-CPL)") (class "Default")
      (node (ref "C55") (pin "2") (pinfunction "2_2") (pintype "passive"))
      (node (ref "U8") (pin "1") (pinfunction "CPL_1") (pintype "passive"))
    )
    (net (code "79") (name "Net-(U8-DVDD)") (class "Default")
      (node (ref "C56") (pin "2") (pinfunction "2_2") (pintype "passive"))
      (node (ref "U8") (pin "33") (pinfunction "DVDD_33") (pintype "passive"))
    )
    (net (code "80") (name "Net-(U8-VCP)") (class "Default")
      (node (ref "C51") (pin "1") (pinfunction "1_1") (pintype "passive"))
      (node (ref "U8") (pin "3") (pinfunction "VCP_3") (pintype "passive"))
    )
    (net (code "81") (name "PGND") (class "Default")
      (node (ref "C31") (pin "1") (pinfunction "1_1") (pintype "passive"))
      (node (ref "C32") (pin "1") (pinfunction "1_1") (pintype "passive"))
      (node (ref "C34") (pin "1") (pinfunction "1_1") (pintype "passive"))
      (node (ref "C35") (pin "1") (pinfunction "1_1") (pintype "passive"))
      (node (ref "C36") (pin "1") (pinfunction "1_1") (pintype "passive"))
      (node (ref "C40") (pin "1") (pinfunction "1_1") (pintype "passive"))
      (node (ref "C41") (pin "1") (pinfunction "1_1") (pintype "passive"))
      (node (ref "C42") (pin "1") (pinfunction "1_1") (pintype "passive"))
      (node (ref "C43") (pin "2") (pinfunction "2_2") (pintype "passive"))
      (node (ref "C44") (pin "2") (pinfunction "2_2") (pintype "passive"))
      (node (ref "C45") (pin "2") (pinfunction "2_2") (pintype "passive"))
      (node (ref "C46") (pin "1") (pinfunction "1_1") (pintype "passive"))
      (node (ref "C47") (pin "1") (pinfunction "1_1") (pintype "passive"))
      (node (ref "C48") (pin "1") (pinfunction "1_1") (pintype "passive"))
      (node (ref "C49") (pin "1") (pinfunction "1_1") (pintype "passive"))
      (node (ref "C50") (pin "1") (pinfunction "1_1") (pintype "passive"))
      (node (ref "C52") (pin "1") (pinfunction "1_1") (pintype "passive"))
      (node (ref "C53") (pin "1") (pinfunction "1_1") (pintype "passive"))
      (node (ref "C54") (pin "1") (pinfunction "1_1") (pintype "passive"))
      (node (ref "C58") (pin "1") (pinfunction "1_1") (pintype "passive"))
      (node (ref "C59") (pin "1") (pinfunction "1_1") (pintype "passive"))
      (node (ref "C60") (pin "1") (pinfunction "1_1") (pintype "passive"))
      (node (ref "C61") (pin "2") (pinfunction "2_2") (pintype "passive"))
      (node (ref "C62") (pin "2") (pinfunction "2_2") (pintype "passive"))
      (node (ref "C63") (pin "2") (pinfunction "2_2") (pintype "passive"))
      (node (ref "C64") (pin "1") (pinfunction "1_1") (pintype "passive"))
      (node (ref "C65") (pin "1") (pinfunction "1_1") (pintype "passive"))
      (node (ref "C66") (pin "1") (pinfunction "1_1") (pintype "passive"))
      (node (ref "C67") (pin "1") (pinfunction "1_1") (pintype "passive"))
      (node (ref "R34") (pin "1") (pinfunction "1_1") (pintype "passive"))
      (node (ref "R35") (pin "1") (pinfunction "1_1") (pintype "passive"))
      (node (ref "R36") (pin "1") (pinfunction "1_1") (pintype "passive"))
      (node (ref "R37") (pin "1") (pinfunction "1_1") (pintype "passive"))
      (node (ref "R38") (pin "1") (pinfunction "1_1") (pintype "passive"))
      (node (ref "R39") (pin "1") (pinfunction "1_1") (pintype "passive"))
      (node (ref "R55") (pin "1") (pinfunction "1_1") (pintype "passive"))
      (node (ref "R56") (pin "1") (pinfunction "1_1") (pintype "passive"))
      (node (ref "R57") (pin "1") (pinfunction "1_1") (pintype "passive"))
      (node (ref "R58") (pin "1") (pinfunction "1_1") (pintype "passive"))
      (node (ref "R59") (pin "1") (pinfunction "1_1") (pintype "passive"))
      (node (ref "R60") (pin "1") (pinfunction "1_1") (pintype "passive"))
      (node (ref "R74") (pin "2") (pinfunction "2_2") (pintype "passive"))
      (node (ref "TP12") (pin "1") (pintype "passive"))
      (node (ref "U7") (pin "10") (pinfunction "SNA_10") (pintype "passive"))
      (node (ref "U7") (pin "11") (pinfunction "SNB_11") (pintype "passive"))
      (node (ref "U7") (pin "20") (pinfunction "SNC_20") (pintype "passive"))
      (node (ref "U7") (pin "40") (pinfunction "PGND_40") (pintype "passive"))
      (node (ref "U7") (pin "41") (pinfunction "EP_41") (pintype "passive"))
      (node (ref "U8") (pin "10") (pinfunction "SNA_10") (pintype "passive"))
      (node (ref "U8") (pin "11") (pinfunction "SNB_11") (pintype "passive"))
      (node (ref "U8") (pin "20") (pinfunction "SNC_20") (pintype "passive"))
      (node (ref "U8") (pin "40") (pinfunction "PGND_40") (pintype "passive"))
      (node (ref "U8") (pin "41") (pinfunction "EP_41") (pintype "passive"))
    )
    (net (code "82") (name "VCC_3V3_M1") (class "Default")
      (node (ref "C39") (pin "2") (pinfunction "2_2") (pintype "passive"))
      (node (ref "C57") (pin "2") (pinfunction "2_2") (pintype "passive"))
      (node (ref "LED2") (pin "1") (pinfunction "+_1") (pintype "passive"))
      (node (ref "LED3") (pin "1") (pinfunction "+_1") (pintype "passive"))
      (node (ref "R42") (pin "1") (pinfunction "1_1") (pintype "passive"))
      (node (ref "R43") (pin "1") (pinfunction "1_1") (pintype "passive"))
      (node (ref "R45") (pin "1") (pinfunction "1_1") (pintype "passive"))
      (node (ref "R49") (pin "1") (pinfunction "1_1") (pintype "passive"))
      (node (ref "R63") (pin "1") (pinfunction "1_1") (pintype "passive"))
      (node (ref "R64") (pin "1") (pinfunction "1_1") (pintype "passive"))
      (node (ref "R66") (pin "1") (pinfunction "1_1") (pintype "passive"))
      (node (ref "R70") (pin "1") (pinfunction "1_1") (pintype "passive"))
      (node (ref "U7") (pin "24") (pinfunction "VREF_24") (pintype "passive"))
      (node (ref "U8") (pin "24") (pinfunction "VREF_24") (pintype "passive"))
    )
    (net (code "83") (name "VM") (class "Default")
      (node (ref "C31") (pin "2") (pinfunction "2_2") (pintype "passive"))
      (node (ref "C32") (pin "2") (pinfunction "2_2") (pintype "passive"))
      (node (ref "C33") (pin "2") (pinfunction "2_2") (pintype "passive"))
      (node (ref "C34") (pin "2") (pinfunction "2_2") (pintype "passive"))
      (node (ref "C35") (pin "2") (pinfunction "2_2") (pintype "passive"))
      (node (ref "C36") (pin "2") (pinfunction "2_2") (pintype "passive"))
      (node (ref "C49") (pin "2") (pinfunction "2_2") (pintype "passive"))
      (node (ref "C50") (pin "2") (pinfunction "2_2") (pintype "passive"))
      (node (ref "C51") (pin "2") (pinfunction "2_2") (pintype "passive"))
      (node (ref "C52") (pin "2") (pinfunction "2_2") (pintype "passive"))
      (node (ref "C53") (pin "2") (pinfunction "2_2") (pintype "passive"))
      (node (ref "C54") (pin "2") (pinfunction "2_2") (pintype "passive"))
      (node (ref "Q1") (pin "5") (pinfunction "D2_5") (pintype "passive"))
      (node (ref "Q1") (pin "6") (pinfunction "D2_6") (pintype "passive"))
      (node (ref "Q2") (pin "5") (pinfunction "D2_5") (pintype "passive"))
      (node (ref "Q2") (pin "6") (pinfunction "D2_6") (pintype "passive"))
      (node (ref "Q3") (pin "5") (pinfunction "D2_5") (pintype "passive"))
      (node (ref "Q3") (pin "6") (pinfunction "D2_6") (pintype "passive"))
      (node (ref "Q4") (pin "5") (pinfunction "D2_5") (pintype "passive"))
      (node (ref "Q4") (pin "6") (pinfunction "D2_6") (pintype "passive"))
      (node (ref "Q5") (pin "5") (pinfunction "D2_5") (pintype "passive"))
      (node (ref "Q5") (pin "6") (pinfunction "D2_6") (pintype "passive"))
      (node (ref "Q6") (pin "5") (pinfunction "D2_5") (pintype "passive"))
      (node (ref "Q6") (pin "6") (pinfunction "D2_6") (pintype "passive"))
      (node (ref "R73") (pin "1") (pinfunction "1_1") (pintype "passive"))
      (node (ref "TP11") (pin "1") (pintype "passive"))
      (node (ref "U7") (pin "4") (pinfunction "VM_4") (pintype "passive"))
      (node (ref "U7") (pin "5") (pinfunction "VDRAIN_5") (pintype "passive"))
      (node (ref "U8") (pin "4") (pinfunction "VM_4") (pintype "passive"))
      (node (ref "U8") (pin "5") (pinfunction "VDRAIN_5") (pintype "passive"))
    )
  )
)
